# FAL65816_Backplane.net
KiCad netlist of a schematic drawn in EAGLE
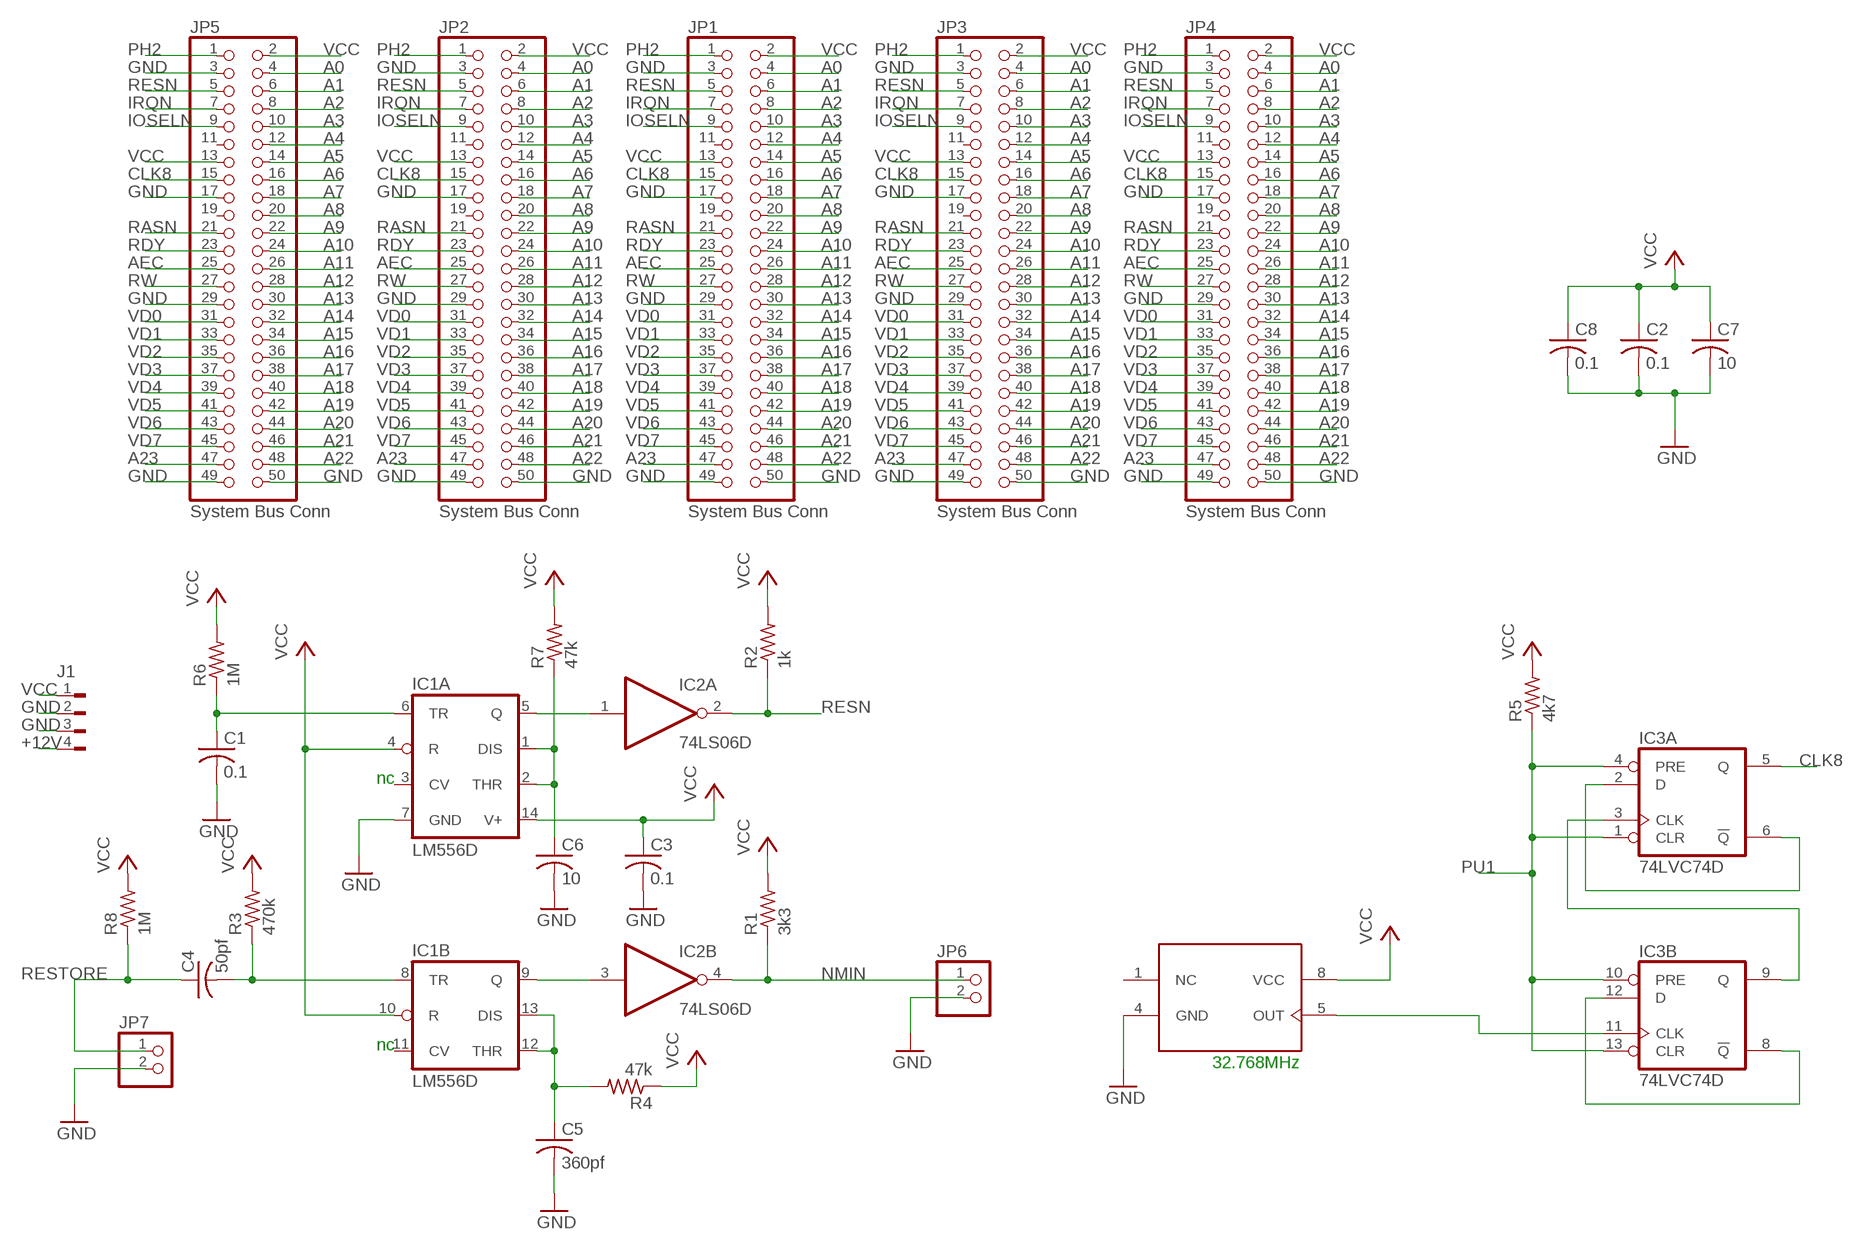
[diagram p0: schematic, sheet 1]

(export (version "E")
  (design (tool "Eeschema 10.0.6"))
  (components
    (comp (ref "C1")
      (value "0.1")
      (footprint "eagle-import:C050-024X044")
      (libsource (lib "eagle-import") (part "C-US050-024X044"))
    )
    (comp (ref "C2")
      (value "0.1")
      (footprint "eagle-import:C050-024X044")
      (libsource (lib "eagle-import") (part "C-US050-024X044"))
    )
    (comp (ref "C3")
      (value "0.1")
      (footprint "eagle-import:C050-024X044")
      (libsource (lib "eagle-import") (part "C-US050-024X044"))
    )
    (comp (ref "C4")
      (value "50pf")
      (footprint "eagle-import:C050-024X044")
      (libsource (lib "eagle-import") (part "C-US050-024X044"))
    )
    (comp (ref "C5")
      (value "360pf")
      (footprint "eagle-import:C050-024X044")
      (libsource (lib "eagle-import") (part "C-US050-024X044"))
    )
    (comp (ref "C6")
      (value "10")
      (footprint "eagle-import:C050-024X044")
      (libsource (lib "eagle-import") (part "C-US050-024X044"))
    )
    (comp (ref "C7")
      (value "10")
      (footprint "eagle-import:C050-024X044")
      (libsource (lib "eagle-import") (part "C-US050-024X044"))
    )
    (comp (ref "C8")
      (value "0.1")
      (footprint "eagle-import:C050-024X044")
      (libsource (lib "eagle-import") (part "C-US050-024X044"))
    )
    (comp (ref "IC1")
      (value "LM556D")
      (footprint "eagle-import:SO14")
      (libsource (lib "eagle-import") (part "556DLM"))
    )
    (comp (ref "IC2")
      (value "74LS06D")
      (footprint "eagle-import:SO14")
      (libsource (lib "eagle-import") (part "7406DLS"))
    )
    (comp (ref "IC3")
      (value "74LVC74D")
      (footprint "eagle-import:SO14")
      (libsource (lib "eagle-import") (part "7474DLS"))
    )
    (comp (ref "J1")
      (value "FLOPPY-4")
      (footprint "eagle-import:FLOPPY-4")
      (libsource (lib "eagle-import") (part "FLOPPY-4"))
    )
    (comp (ref "JP1")
      (value "System Bus Conn")
      (footprint "eagle-import:2X25")
      (libsource (lib "eagle-import") (part "PINHD-2X25"))
    )
    (comp (ref "JP2")
      (value "System Bus Conn")
      (footprint "eagle-import:2X25")
      (libsource (lib "eagle-import") (part "PINHD-2X25"))
    )
    (comp (ref "JP3")
      (value "System Bus Conn")
      (footprint "eagle-import:2X25")
      (libsource (lib "eagle-import") (part "PINHD-2X25"))
    )
    (comp (ref "JP4")
      (value "System Bus Conn")
      (footprint "eagle-import:2X25")
      (libsource (lib "eagle-import") (part "PINHD-2X25"))
    )
    (comp (ref "JP5")
      (value "System Bus Conn")
      (footprint "eagle-import:2X25")
      (libsource (lib "eagle-import") (part "PINHD-2X25"))
    )
    (comp (ref "JP6")
      (value "PINHD-1X2")
      (footprint "eagle-import:1X02")
      (libsource (lib "eagle-import") (part "PINHD-1X2"))
    )
    (comp (ref "JP7")
      (value "PINHD-1X2")
      (footprint "eagle-import:1X02")
      (libsource (lib "eagle-import") (part "PINHD-1X2"))
    )
    (comp (ref "R1")
      (value "3k3")
      (footprint "eagle-import:0204_7")
      (libsource (lib "eagle-import") (part "R-US_0204/7"))
    )
    (comp (ref "R2")
      (value "1k")
      (footprint "eagle-import:0204_7")
      (libsource (lib "eagle-import") (part "R-US_0204/7"))
    )
    (comp (ref "R3")
      (value "470k")
      (footprint "eagle-import:0204_7")
      (libsource (lib "eagle-import") (part "R-US_0204/7"))
    )
    (comp (ref "R4")
      (value "47k")
      (footprint "eagle-import:0204_7")
      (libsource (lib "eagle-import") (part "R-US_0204/7"))
    )
    (comp (ref "R5")
      (value "4k7")
      (footprint "eagle-import:0204_7")
      (libsource (lib "eagle-import") (part "R-US_0204/7"))
    )
    (comp (ref "R6")
      (value "1M")
      (footprint "eagle-import:0204_7")
      (libsource (lib "eagle-import") (part "R-US_0204/7"))
    )
    (comp (ref "R7")
      (value "47k")
      (footprint "eagle-import:0204_7")
      (libsource (lib "eagle-import") (part "R-US_0204/7"))
    )
    (comp (ref "R8")
      (value "1M")
      (footprint "eagle-import:0204_7")
      (libsource (lib "eagle-import") (part "R-US_0204/7"))
    )
    (comp (ref "U$1")
      (value "OSC")
      (footprint "eagle-import:DIL08")
      (libsource (lib "eagle-import") (part "OSC"))
    )
  )
  (nets
    (net (code "1") (name "/+12V") (class "Default")
      (node (ref "J1") (pin "4") (pinfunction "4_4") (pintype "passive"))
    )
    (net (code "2") (name "/A0") (class "Default")
      (node (ref "JP1") (pin "4") (pinfunction "4_4") (pintype "passive"))
      (node (ref "JP2") (pin "4") (pinfunction "4_4") (pintype "passive"))
      (node (ref "JP3") (pin "4") (pinfunction "4_4") (pintype "passive"))
      (node (ref "JP4") (pin "4") (pinfunction "4_4") (pintype "passive"))
      (node (ref "JP5") (pin "4") (pinfunction "4_4") (pintype "passive"))
    )
    (net (code "3") (name "/A1") (class "Default")
      (node (ref "JP1") (pin "6") (pinfunction "6_6") (pintype "passive"))
      (node (ref "JP2") (pin "6") (pinfunction "6_6") (pintype "passive"))
      (node (ref "JP3") (pin "6") (pinfunction "6_6") (pintype "passive"))
      (node (ref "JP4") (pin "6") (pinfunction "6_6") (pintype "passive"))
      (node (ref "JP5") (pin "6") (pinfunction "6_6") (pintype "passive"))
    )
    (net (code "4") (name "/A2") (class "Default")
      (node (ref "JP1") (pin "8") (pinfunction "8_8") (pintype "passive"))
      (node (ref "JP2") (pin "8") (pinfunction "8_8") (pintype "passive"))
      (node (ref "JP3") (pin "8") (pinfunction "8_8") (pintype "passive"))
      (node (ref "JP4") (pin "8") (pinfunction "8_8") (pintype "passive"))
      (node (ref "JP5") (pin "8") (pinfunction "8_8") (pintype "passive"))
    )
    (net (code "5") (name "/A3") (class "Default")
      (node (ref "JP1") (pin "10") (pinfunction "10_10") (pintype "passive"))
      (node (ref "JP2") (pin "10") (pinfunction "10_10") (pintype "passive"))
      (node (ref "JP3") (pin "10") (pinfunction "10_10") (pintype "passive"))
      (node (ref "JP4") (pin "10") (pinfunction "10_10") (pintype "passive"))
      (node (ref "JP5") (pin "10") (pinfunction "10_10") (pintype "passive"))
    )
    (net (code "6") (name "/A4") (class "Default")
      (node (ref "JP1") (pin "12") (pinfunction "12_12") (pintype "passive"))
      (node (ref "JP2") (pin "12") (pinfunction "12_12") (pintype "passive"))
      (node (ref "JP3") (pin "12") (pinfunction "12_12") (pintype "passive"))
      (node (ref "JP4") (pin "12") (pinfunction "12_12") (pintype "passive"))
      (node (ref "JP5") (pin "12") (pinfunction "12_12") (pintype "passive"))
    )
    (net (code "7") (name "/A5") (class "Default")
      (node (ref "JP1") (pin "14") (pinfunction "14_14") (pintype "passive"))
      (node (ref "JP2") (pin "14") (pinfunction "14_14") (pintype "passive"))
      (node (ref "JP3") (pin "14") (pinfunction "14_14") (pintype "passive"))
      (node (ref "JP4") (pin "14") (pinfunction "14_14") (pintype "passive"))
      (node (ref "JP5") (pin "14") (pinfunction "14_14") (pintype "passive"))
    )
    (net (code "8") (name "/A6") (class "Default")
      (node (ref "JP1") (pin "16") (pinfunction "16_16") (pintype "passive"))
      (node (ref "JP2") (pin "16") (pinfunction "16_16") (pintype "passive"))
      (node (ref "JP3") (pin "16") (pinfunction "16_16") (pintype "passive"))
      (node (ref "JP4") (pin "16") (pinfunction "16_16") (pintype "passive"))
      (node (ref "JP5") (pin "16") (pinfunction "16_16") (pintype "passive"))
    )
    (net (code "9") (name "/A7") (class "Default")
      (node (ref "JP1") (pin "18") (pinfunction "18_18") (pintype "passive"))
      (node (ref "JP2") (pin "18") (pinfunction "18_18") (pintype "passive"))
      (node (ref "JP3") (pin "18") (pinfunction "18_18") (pintype "passive"))
      (node (ref "JP4") (pin "18") (pinfunction "18_18") (pintype "passive"))
      (node (ref "JP5") (pin "18") (pinfunction "18_18") (pintype "passive"))
    )
    (net (code "10") (name "/A8") (class "Default")
      (node (ref "JP1") (pin "20") (pinfunction "20_20") (pintype "passive"))
      (node (ref "JP2") (pin "20") (pinfunction "20_20") (pintype "passive"))
      (node (ref "JP3") (pin "20") (pinfunction "20_20") (pintype "passive"))
      (node (ref "JP4") (pin "20") (pinfunction "20_20") (pintype "passive"))
      (node (ref "JP5") (pin "20") (pinfunction "20_20") (pintype "passive"))
    )
    (net (code "11") (name "/A9") (class "Default")
      (node (ref "JP1") (pin "22") (pinfunction "22_22") (pintype "passive"))
      (node (ref "JP2") (pin "22") (pinfunction "22_22") (pintype "passive"))
      (node (ref "JP3") (pin "22") (pinfunction "22_22") (pintype "passive"))
      (node (ref "JP4") (pin "22") (pinfunction "22_22") (pintype "passive"))
      (node (ref "JP5") (pin "22") (pinfunction "22_22") (pintype "passive"))
    )
    (net (code "12") (name "/A10") (class "Default")
      (node (ref "JP1") (pin "24") (pinfunction "24_24") (pintype "passive"))
      (node (ref "JP2") (pin "24") (pinfunction "24_24") (pintype "passive"))
      (node (ref "JP3") (pin "24") (pinfunction "24_24") (pintype "passive"))
      (node (ref "JP4") (pin "24") (pinfunction "24_24") (pintype "passive"))
      (node (ref "JP5") (pin "24") (pinfunction "24_24") (pintype "passive"))
    )
    (net (code "13") (name "/A11") (class "Default")
      (node (ref "JP1") (pin "26") (pinfunction "26_26") (pintype "passive"))
      (node (ref "JP2") (pin "26") (pinfunction "26_26") (pintype "passive"))
      (node (ref "JP3") (pin "26") (pinfunction "26_26") (pintype "passive"))
      (node (ref "JP4") (pin "26") (pinfunction "26_26") (pintype "passive"))
      (node (ref "JP5") (pin "26") (pinfunction "26_26") (pintype "passive"))
    )
    (net (code "14") (name "/A12") (class "Default")
      (node (ref "JP1") (pin "28") (pinfunction "28_28") (pintype "passive"))
      (node (ref "JP2") (pin "28") (pinfunction "28_28") (pintype "passive"))
      (node (ref "JP3") (pin "28") (pinfunction "28_28") (pintype "passive"))
      (node (ref "JP4") (pin "28") (pinfunction "28_28") (pintype "passive"))
      (node (ref "JP5") (pin "28") (pinfunction "28_28") (pintype "passive"))
    )
    (net (code "15") (name "/A13") (class "Default")
      (node (ref "JP1") (pin "30") (pinfunction "30_30") (pintype "passive"))
      (node (ref "JP2") (pin "30") (pinfunction "30_30") (pintype "passive"))
      (node (ref "JP3") (pin "30") (pinfunction "30_30") (pintype "passive"))
      (node (ref "JP4") (pin "30") (pinfunction "30_30") (pintype "passive"))
      (node (ref "JP5") (pin "30") (pinfunction "30_30") (pintype "passive"))
    )
    (net (code "16") (name "/A14") (class "Default")
      (node (ref "JP1") (pin "32") (pinfunction "32_32") (pintype "passive"))
      (node (ref "JP2") (pin "32") (pinfunction "32_32") (pintype "passive"))
      (node (ref "JP3") (pin "32") (pinfunction "32_32") (pintype "passive"))
      (node (ref "JP4") (pin "32") (pinfunction "32_32") (pintype "passive"))
      (node (ref "JP5") (pin "32") (pinfunction "32_32") (pintype "passive"))
    )
    (net (code "17") (name "/A15") (class "Default")
      (node (ref "JP1") (pin "34") (pinfunction "34_34") (pintype "passive"))
      (node (ref "JP2") (pin "34") (pinfunction "34_34") (pintype "passive"))
      (node (ref "JP3") (pin "34") (pinfunction "34_34") (pintype "passive"))
      (node (ref "JP4") (pin "34") (pinfunction "34_34") (pintype "passive"))
      (node (ref "JP5") (pin "34") (pinfunction "34_34") (pintype "passive"))
    )
    (net (code "18") (name "/A16") (class "Default")
      (node (ref "JP1") (pin "36") (pinfunction "36_36") (pintype "passive"))
      (node (ref "JP2") (pin "36") (pinfunction "36_36") (pintype "passive"))
      (node (ref "JP3") (pin "36") (pinfunction "36_36") (pintype "passive"))
      (node (ref "JP4") (pin "36") (pinfunction "36_36") (pintype "passive"))
      (node (ref "JP5") (pin "36") (pinfunction "36_36") (pintype "passive"))
    )
    (net (code "19") (name "/A17") (class "Default")
      (node (ref "JP1") (pin "38") (pinfunction "38_38") (pintype "passive"))
      (node (ref "JP2") (pin "38") (pinfunction "38_38") (pintype "passive"))
      (node (ref "JP3") (pin "38") (pinfunction "38_38") (pintype "passive"))
      (node (ref "JP4") (pin "38") (pinfunction "38_38") (pintype "passive"))
      (node (ref "JP5") (pin "38") (pinfunction "38_38") (pintype "passive"))
    )
    (net (code "20") (name "/A18") (class "Default")
      (node (ref "JP1") (pin "40") (pinfunction "40_40") (pintype "passive"))
      (node (ref "JP2") (pin "40") (pinfunction "40_40") (pintype "passive"))
      (node (ref "JP3") (pin "40") (pinfunction "40_40") (pintype "passive"))
      (node (ref "JP4") (pin "40") (pinfunction "40_40") (pintype "passive"))
      (node (ref "JP5") (pin "40") (pinfunction "40_40") (pintype "passive"))
    )
    (net (code "21") (name "/A19") (class "Default")
      (node (ref "JP1") (pin "42") (pinfunction "42_42") (pintype "passive"))
      (node (ref "JP2") (pin "42") (pinfunction "42_42") (pintype "passive"))
      (node (ref "JP3") (pin "42") (pinfunction "42_42") (pintype "passive"))
      (node (ref "JP4") (pin "42") (pinfunction "42_42") (pintype "passive"))
      (node (ref "JP5") (pin "42") (pinfunction "42_42") (pintype "passive"))
    )
    (net (code "22") (name "/A20") (class "Default")
      (node (ref "JP1") (pin "44") (pinfunction "44_44") (pintype "passive"))
      (node (ref "JP2") (pin "44") (pinfunction "44_44") (pintype "passive"))
      (node (ref "JP3") (pin "44") (pinfunction "44_44") (pintype "passive"))
      (node (ref "JP4") (pin "44") (pinfunction "44_44") (pintype "passive"))
      (node (ref "JP5") (pin "44") (pinfunction "44_44") (pintype "passive"))
    )
    (net (code "23") (name "/A21") (class "Default")
      (node (ref "JP1") (pin "46") (pinfunction "46_46") (pintype "passive"))
      (node (ref "JP2") (pin "46") (pinfunction "46_46") (pintype "passive"))
      (node (ref "JP3") (pin "46") (pinfunction "46_46") (pintype "passive"))
      (node (ref "JP4") (pin "46") (pinfunction "46_46") (pintype "passive"))
      (node (ref "JP5") (pin "46") (pinfunction "46_46") (pintype "passive"))
    )
    (net (code "24") (name "/A22") (class "Default")
      (node (ref "JP1") (pin "48") (pinfunction "48_48") (pintype "passive"))
      (node (ref "JP2") (pin "48") (pinfunction "48_48") (pintype "passive"))
      (node (ref "JP3") (pin "48") (pinfunction "48_48") (pintype "passive"))
      (node (ref "JP4") (pin "48") (pinfunction "48_48") (pintype "passive"))
      (node (ref "JP5") (pin "48") (pinfunction "48_48") (pintype "passive"))
    )
    (net (code "25") (name "/A23") (class "Default")
      (node (ref "JP1") (pin "47") (pinfunction "47_47") (pintype "passive"))
      (node (ref "JP2") (pin "47") (pinfunction "47_47") (pintype "passive"))
      (node (ref "JP3") (pin "47") (pinfunction "47_47") (pintype "passive"))
      (node (ref "JP4") (pin "47") (pinfunction "47_47") (pintype "passive"))
      (node (ref "JP5") (pin "47") (pinfunction "47_47") (pintype "passive"))
    )
    (net (code "26") (name "/AEC") (class "Default")
      (node (ref "JP1") (pin "25") (pinfunction "25_25") (pintype "passive"))
      (node (ref "JP2") (pin "25") (pinfunction "25_25") (pintype "passive"))
      (node (ref "JP3") (pin "25") (pinfunction "25_25") (pintype "passive"))
      (node (ref "JP4") (pin "25") (pinfunction "25_25") (pintype "passive"))
      (node (ref "JP5") (pin "25") (pinfunction "25_25") (pintype "passive"))
    )
    (net (code "27") (name "/CLK8") (class "Default")
      (node (ref "IC3") (pin "5") (pinfunction "Q_5") (pintype "output"))
      (node (ref "JP1") (pin "15") (pinfunction "15_15") (pintype "passive"))
      (node (ref "JP2") (pin "15") (pinfunction "15_15") (pintype "passive"))
      (node (ref "JP3") (pin "15") (pinfunction "15_15") (pintype "passive"))
      (node (ref "JP4") (pin "15") (pinfunction "15_15") (pintype "passive"))
      (node (ref "JP5") (pin "15") (pinfunction "15_15") (pintype "passive"))
    )
    (net (code "28") (name "/IOSELN") (class "Default")
      (node (ref "JP1") (pin "9") (pinfunction "9_9") (pintype "passive"))
      (node (ref "JP2") (pin "9") (pinfunction "9_9") (pintype "passive"))
      (node (ref "JP3") (pin "9") (pinfunction "9_9") (pintype "passive"))
      (node (ref "JP4") (pin "9") (pinfunction "9_9") (pintype "passive"))
      (node (ref "JP5") (pin "9") (pinfunction "9_9") (pintype "passive"))
    )
    (net (code "29") (name "/IRQN") (class "Default")
      (node (ref "JP1") (pin "7") (pinfunction "7_7") (pintype "passive"))
      (node (ref "JP2") (pin "7") (pinfunction "7_7") (pintype "passive"))
      (node (ref "JP3") (pin "7") (pinfunction "7_7") (pintype "passive"))
      (node (ref "JP4") (pin "7") (pinfunction "7_7") (pintype "passive"))
      (node (ref "JP5") (pin "7") (pinfunction "7_7") (pintype "passive"))
    )
    (net (code "30") (name "/NMIN") (class "Default")
      (node (ref "IC2") (pin "4") (pinfunction "O_4") (pintype "open_collector"))
      (node (ref "JP6") (pin "1") (pinfunction "1_1") (pintype "passive"))
      (node (ref "R1") (pin "1") (pinfunction "1_1") (pintype "passive"))
    )
    (net (code "31") (name "/PH2") (class "Default")
      (node (ref "JP1") (pin "1") (pinfunction "1_1") (pintype "passive"))
      (node (ref "JP2") (pin "1") (pinfunction "1_1") (pintype "passive"))
      (node (ref "JP3") (pin "1") (pinfunction "1_1") (pintype "passive"))
      (node (ref "JP4") (pin "1") (pinfunction "1_1") (pintype "passive"))
      (node (ref "JP5") (pin "1") (pinfunction "1_1") (pintype "passive"))
    )
    (net (code "32") (name "/PU1") (class "Default")
      (node (ref "IC3") (pin "1") (pinfunction "CLR_1") (pintype "input"))
      (node (ref "IC3") (pin "10") (pinfunction "PRE_10") (pintype "input"))
      (node (ref "IC3") (pin "13") (pinfunction "CLR_13") (pintype "input"))
      (node (ref "IC3") (pin "4") (pinfunction "PRE_4") (pintype "input"))
      (node (ref "R5") (pin "1") (pinfunction "1_1") (pintype "passive"))
    )
    (net (code "33") (name "/RASN") (class "Default")
      (node (ref "JP1") (pin "21") (pinfunction "21_21") (pintype "passive"))
      (node (ref "JP2") (pin "21") (pinfunction "21_21") (pintype "passive"))
      (node (ref "JP3") (pin "21") (pinfunction "21_21") (pintype "passive"))
      (node (ref "JP4") (pin "21") (pinfunction "21_21") (pintype "passive"))
      (node (ref "JP5") (pin "21") (pinfunction "21_21") (pintype "passive"))
    )
    (net (code "34") (name "/RDY") (class "Default")
      (node (ref "JP1") (pin "23") (pinfunction "23_23") (pintype "passive"))
      (node (ref "JP2") (pin "23") (pinfunction "23_23") (pintype "passive"))
      (node (ref "JP3") (pin "23") (pinfunction "23_23") (pintype "passive"))
      (node (ref "JP4") (pin "23") (pinfunction "23_23") (pintype "passive"))
      (node (ref "JP5") (pin "23") (pinfunction "23_23") (pintype "passive"))
    )
    (net (code "35") (name "/RESN") (class "Default")
      (node (ref "IC2") (pin "2") (pinfunction "O_2") (pintype "open_collector"))
      (node (ref "JP1") (pin "5") (pinfunction "5_5") (pintype "passive"))
      (node (ref "JP2") (pin "5") (pinfunction "5_5") (pintype "passive"))
      (node (ref "JP3") (pin "5") (pinfunction "5_5") (pintype "passive"))
      (node (ref "JP4") (pin "5") (pinfunction "5_5") (pintype "passive"))
      (node (ref "JP5") (pin "5") (pinfunction "5_5") (pintype "passive"))
      (node (ref "R2") (pin "1") (pinfunction "1_1") (pintype "passive"))
    )
    (net (code "36") (name "/RESTORE") (class "Default")
      (node (ref "C4") (pin "1") (pinfunction "1_1") (pintype "passive"))
      (node (ref "JP7") (pin "1") (pinfunction "1_1") (pintype "passive"))
      (node (ref "R8") (pin "1") (pinfunction "1_1") (pintype "passive"))
    )
    (net (code "37") (name "/RW") (class "Default")
      (node (ref "JP1") (pin "27") (pinfunction "27_27") (pintype "passive"))
      (node (ref "JP2") (pin "27") (pinfunction "27_27") (pintype "passive"))
      (node (ref "JP3") (pin "27") (pinfunction "27_27") (pintype "passive"))
      (node (ref "JP4") (pin "27") (pinfunction "27_27") (pintype "passive"))
      (node (ref "JP5") (pin "27") (pinfunction "27_27") (pintype "passive"))
    )
    (net (code "38") (name "/VD0") (class "Default")
      (node (ref "JP1") (pin "31") (pinfunction "31_31") (pintype "passive"))
      (node (ref "JP2") (pin "31") (pinfunction "31_31") (pintype "passive"))
      (node (ref "JP3") (pin "31") (pinfunction "31_31") (pintype "passive"))
      (node (ref "JP4") (pin "31") (pinfunction "31_31") (pintype "passive"))
      (node (ref "JP5") (pin "31") (pinfunction "31_31") (pintype "passive"))
    )
    (net (code "39") (name "/VD1") (class "Default")
      (node (ref "JP1") (pin "33") (pinfunction "33_33") (pintype "passive"))
      (node (ref "JP2") (pin "33") (pinfunction "33_33") (pintype "passive"))
      (node (ref "JP3") (pin "33") (pinfunction "33_33") (pintype "passive"))
      (node (ref "JP4") (pin "33") (pinfunction "33_33") (pintype "passive"))
      (node (ref "JP5") (pin "33") (pinfunction "33_33") (pintype "passive"))
    )
    (net (code "40") (name "/VD2") (class "Default")
      (node (ref "JP1") (pin "35") (pinfunction "35_35") (pintype "passive"))
      (node (ref "JP2") (pin "35") (pinfunction "35_35") (pintype "passive"))
      (node (ref "JP3") (pin "35") (pinfunction "35_35") (pintype "passive"))
      (node (ref "JP4") (pin "35") (pinfunction "35_35") (pintype "passive"))
      (node (ref "JP5") (pin "35") (pinfunction "35_35") (pintype "passive"))
    )
    (net (code "41") (name "/VD3") (class "Default")
      (node (ref "JP1") (pin "37") (pinfunction "37_37") (pintype "passive"))
      (node (ref "JP2") (pin "37") (pinfunction "37_37") (pintype "passive"))
      (node (ref "JP3") (pin "37") (pinfunction "37_37") (pintype "passive"))
      (node (ref "JP4") (pin "37") (pinfunction "37_37") (pintype "passive"))
      (node (ref "JP5") (pin "37") (pinfunction "37_37") (pintype "passive"))
    )
    (net (code "42") (name "/VD4") (class "Default")
      (node (ref "JP1") (pin "39") (pinfunction "39_39") (pintype "passive"))
      (node (ref "JP2") (pin "39") (pinfunction "39_39") (pintype "passive"))
      (node (ref "JP3") (pin "39") (pinfunction "39_39") (pintype "passive"))
      (node (ref "JP4") (pin "39") (pinfunction "39_39") (pintype "passive"))
      (node (ref "JP5") (pin "39") (pinfunction "39_39") (pintype "passive"))
    )
    (net (code "43") (name "/VD5") (class "Default")
      (node (ref "JP1") (pin "41") (pinfunction "41_41") (pintype "passive"))
      (node (ref "JP2") (pin "41") (pinfunction "41_41") (pintype "passive"))
      (node (ref "JP3") (pin "41") (pinfunction "41_41") (pintype "passive"))
      (node (ref "JP4") (pin "41") (pinfunction "41_41") (pintype "passive"))
      (node (ref "JP5") (pin "41") (pinfunction "41_41") (pintype "passive"))
    )
    (net (code "44") (name "/VD6") (class "Default")
      (node (ref "JP1") (pin "43") (pinfunction "43_43") (pintype "passive"))
      (node (ref "JP2") (pin "43") (pinfunction "43_43") (pintype "passive"))
      (node (ref "JP3") (pin "43") (pinfunction "43_43") (pintype "passive"))
      (node (ref "JP4") (pin "43") (pinfunction "43_43") (pintype "passive"))
      (node (ref "JP5") (pin "43") (pinfunction "43_43") (pintype "passive"))
    )
    (net (code "45") (name "/VD7") (class "Default")
      (node (ref "JP1") (pin "45") (pinfunction "45_45") (pintype "passive"))
      (node (ref "JP2") (pin "45") (pinfunction "45_45") (pintype "passive"))
      (node (ref "JP3") (pin "45") (pinfunction "45_45") (pintype "passive"))
      (node (ref "JP4") (pin "45") (pinfunction "45_45") (pintype "passive"))
      (node (ref "JP5") (pin "45") (pinfunction "45_45") (pintype "passive"))
    )
    (net (code "46") (name "GND") (class "Default")
      (node (ref "C1") (pin "2") (pinfunction "2_2") (pintype "passive"))
      (node (ref "C2") (pin "2") (pinfunction "2_2") (pintype "passive"))
      (node (ref "C3") (pin "2") (pinfunction "2_2") (pintype "passive"))
      (node (ref "C5") (pin "2") (pinfunction "2_2") (pintype "passive"))
      (node (ref "C6") (pin "2") (pinfunction "2_2") (pintype "passive"))
      (node (ref "C7") (pin "2") (pinfunction "2_2") (pintype "passive"))
      (node (ref "C8") (pin "2") (pinfunction "2_2") (pintype "passive"))
      (node (ref "IC1") (pin "7") (pinfunction "GND_7") (pintype "power_in"))
      (node (ref "J1") (pin "2") (pinfunction "2_2") (pintype "passive"))
      (node (ref "J1") (pin "3") (pinfunction "3_3") (pintype "passive"))
      (node (ref "JP1") (pin "17") (pinfunction "17_17") (pintype "passive"))
      (node (ref "JP1") (pin "29") (pinfunction "29_29") (pintype "passive"))
      (node (ref "JP1") (pin "3") (pinfunction "3_3") (pintype "passive"))
      (node (ref "JP1") (pin "49") (pinfunction "49_49") (pintype "passive"))
      (node (ref "JP1") (pin "50") (pinfunction "50_50") (pintype "passive"))
      (node (ref "JP2") (pin "17") (pinfunction "17_17") (pintype "passive"))
      (node (ref "JP2") (pin "29") (pinfunction "29_29") (pintype "passive"))
      (node (ref "JP2") (pin "3") (pinfunction "3_3") (pintype "passive"))
      (node (ref "JP2") (pin "49") (pinfunction "49_49") (pintype "passive"))
      (node (ref "JP2") (pin "50") (pinfunction "50_50") (pintype "passive"))
      (node (ref "JP3") (pin "17") (pinfunction "17_17") (pintype "passive"))
      (node (ref "JP3") (pin "29") (pinfunction "29_29") (pintype "passive"))
      (node (ref "JP3") (pin "3") (pinfunction "3_3") (pintype "passive"))
      (node (ref "JP3") (pin "49") (pinfunction "49_49") (pintype "passive"))
      (node (ref "JP3") (pin "50") (pinfunction "50_50") (pintype "passive"))
      (node (ref "JP4") (pin "17") (pinfunction "17_17") (pintype "passive"))
      (node (ref "JP4") (pin "29") (pinfunction "29_29") (pintype "passive"))
      (node (ref "JP4") (pin "3") (pinfunction "3_3") (pintype "passive"))
      (node (ref "JP4") (pin "49") (pinfunction "49_49") (pintype "passive"))
      (node (ref "JP4") (pin "50") (pinfunction "50_50") (pintype "passive"))
      (node (ref "JP5") (pin "17") (pinfunction "17_17") (pintype "passive"))
      (node (ref "JP5") (pin "29") (pinfunction "29_29") (pintype "passive"))
      (node (ref "JP5") (pin "3") (pinfunction "3_3") (pintype "passive"))
      (node (ref "JP5") (pin "49") (pinfunction "49_49") (pintype "passive"))
      (node (ref "JP5") (pin "50") (pinfunction "50_50") (pintype "passive"))
      (node (ref "JP6") (pin "2") (pinfunction "2_2") (pintype "passive"))
      (node (ref "JP7") (pin "2") (pinfunction "2_2") (pintype "passive"))
      (node (ref "U$1") (pin "4") (pinfunction "GND_4") (pintype "power_in"))
    )
    (net (code "47") (name "Net-(IC1A-DIS)") (class "Default")
      (node (ref "C6") (pin "1") (pinfunction "1_1") (pintype "passive"))
      (node (ref "IC1") (pin "1") (pinfunction "DIS_1") (pintype "input"))
      (node (ref "IC1") (pin "2") (pinfunction "THR_2") (pintype "input"))
      (node (ref "R7") (pin "1") (pinfunction "1_1") (pintype "passive"))
    )
    (net (code "48") (name "Net-(IC1A-Q)") (class "Default")
      (node (ref "IC1") (pin "5") (pinfunction "Q_5") (pintype "output"))
      (node (ref "IC2") (pin "1") (pinfunction "I_1") (pintype "input"))
    )
    (net (code "49") (name "Net-(IC1A-TR)") (class "Default")
      (node (ref "C1") (pin "1") (pinfunction "1_1") (pintype "passive"))
      (node (ref "IC1") (pin "6") (pinfunction "TR_6") (pintype "input"))
      (node (ref "R6") (pin "1") (pinfunction "1_1") (pintype "passive"))
    )
    (net (code "50") (name "Net-(IC1B-DIS)") (class "Default")
      (node (ref "C5") (pin "1") (pinfunction "1_1") (pintype "passive"))
      (node (ref "IC1") (pin "12") (pinfunction "THR_12") (pintype "input"))
      (node (ref "IC1") (pin "13") (pinfunction "DIS_13") (pintype "input"))
      (node (ref "R4") (pin "2") (pinfunction "2_2") (pintype "passive"))
    )
    (net (code "51") (name "Net-(IC1B-Q)") (class "Default")
      (node (ref "IC1") (pin "9") (pinfunction "Q_9") (pintype "output"))
      (node (ref "IC2") (pin "3") (pinfunction "I_3") (pintype "input"))
    )
    (net (code "52") (name "Net-(IC1B-TR)") (class "Default")
      (node (ref "C4") (pin "2") (pinfunction "2_2") (pintype "passive"))
      (node (ref "IC1") (pin "8") (pinfunction "TR_8") (pintype "input"))
      (node (ref "R3") (pin "1") (pinfunction "1_1") (pintype "passive"))
    )
    (net (code "53") (name "Net-(IC3A-CLK)") (class "Default")
      (node (ref "IC3") (pin "3") (pinfunction "CLK_3") (pintype "input"))
      (node (ref "IC3") (pin "9") (pinfunction "Q_9") (pintype "output"))
    )
    (net (code "54") (name "Net-(IC3A-D)") (class "Default")
      (node (ref "IC3") (pin "2") (pinfunction "D_2") (pintype "input"))
      (node (ref "IC3") (pin "6") (pinfunction "~{Q}_6") (pintype "output"))
    )
    (net (code "55") (name "Net-(IC3B-CLK)") (class "Default")
      (node (ref "IC3") (pin "11") (pinfunction "CLK_11") (pintype "input"))
      (node (ref "U$1") (pin "5") (pinfunction "OUT_5") (pintype "output"))
    )
    (net (code "56") (name "Net-(IC3B-D)") (class "Default")
      (node (ref "IC3") (pin "12") (pinfunction "D_12") (pintype "input"))
      (node (ref "IC3") (pin "8") (pinfunction "~{Q}_8") (pintype "output"))
    )
    (net (code "57") (name "VCC") (class "Default")
      (node (ref "C2") (pin "1") (pinfunction "1_1") (pintype "passive"))
      (node (ref "C3") (pin "1") (pinfunction "1_1") (pintype "passive"))
      (node (ref "C7") (pin "1") (pinfunction "1_1") (pintype "passive"))
      (node (ref "C8") (pin "1") (pinfunction "1_1") (pintype "passive"))
      (node (ref "IC1") (pin "10") (pinfunction "R_10") (pintype "input"))
      (node (ref "IC1") (pin "14") (pinfunction "V+_14") (pintype "power_in"))
      (node (ref "IC1") (pin "4") (pinfunction "R_4") (pintype "input"))
      (node (ref "J1") (pin "1") (pinfunction "1_1") (pintype "passive"))
      (node (ref "JP1") (pin "13") (pinfunction "13_13") (pintype "passive"))
      (node (ref "JP1") (pin "2") (pinfunction "2_2") (pintype "passive"))
      (node (ref "JP2") (pin "13") (pinfunction "13_13") (pintype "passive"))
      (node (ref "JP2") (pin "2") (pinfunction "2_2") (pintype "passive"))
      (node (ref "JP3") (pin "13") (pinfunction "13_13") (pintype "passive"))
      (node (ref "JP3") (pin "2") (pinfunction "2_2") (pintype "passive"))
      (node (ref "JP4") (pin "13") (pinfunction "13_13") (pintype "passive"))
      (node (ref "JP4") (pin "2") (pinfunction "2_2") (pintype "passive"))
      (node (ref "JP5") (pin "13") (pinfunction "13_13") (pintype "passive"))
      (node (ref "JP5") (pin "2") (pinfunction "2_2") (pintype "passive"))
      (node (ref "R1") (pin "2") (pinfunction "2_2") (pintype "passive"))
      (node (ref "R2") (pin "2") (pinfunction "2_2") (pintype "passive"))
      (node (ref "R3") (pin "2") (pinfunction "2_2") (pintype "passive"))
      (node (ref "R4") (pin "1") (pinfunction "1_1") (pintype "passive"))
      (node (ref "R5") (pin "2") (pinfunction "2_2") (pintype "passive"))
      (node (ref "R6") (pin "2") (pinfunction "2_2") (pintype "passive"))
      (node (ref "R7") (pin "2") (pinfunction "2_2") (pintype "passive"))
      (node (ref "R8") (pin "2") (pinfunction "2_2") (pintype "passive"))
      (node (ref "U$1") (pin "8") (pinfunction "VCC_8") (pintype "power_in"))
    )
    (net (code "58") (name "unconnected-(IC1A-CV-Pad3)") (class "Default")
      (node (ref "IC1") (pin "3") (pinfunction "CV_3") (pintype "input"))
    )
    (net (code "59") (name "unconnected-(IC1B-CV-Pad11)") (class "Default")
      (node (ref "IC1") (pin "11") (pinfunction "CV_11") (pintype "input"))
    )
    (net (code "60") (name "unconnected-(JP1-Pad11)") (class "Default")
      (node (ref "JP1") (pin "11") (pinfunction "11_11") (pintype "passive"))
    )
    (net (code "61") (name "unconnected-(JP1-Pad19)") (class "Default")
      (node (ref "JP1") (pin "19") (pinfunction "19_19") (pintype "passive"))
    )
    (net (code "62") (name "unconnected-(JP2-Pad11)") (class "Default")
      (node (ref "JP2") (pin "11") (pinfunction "11_11") (pintype "passive"))
    )
    (net (code "63") (name "unconnected-(JP2-Pad19)") (class "Default")
      (node (ref "JP2") (pin "19") (pinfunction "19_19") (pintype "passive"))
    )
    (net (code "64") (name "unconnected-(JP3-Pad11)") (class "Default")
      (node (ref "JP3") (pin "11") (pinfunction "11_11") (pintype "passive"))
    )
    (net (code "65") (name "unconnected-(JP3-Pad19)") (class "Default")
      (node (ref "JP3") (pin "19") (pinfunction "19_19") (pintype "passive"))
    )
    (net (code "66") (name "unconnected-(JP4-Pad11)") (class "Default")
      (node (ref "JP4") (pin "11") (pinfunction "11_11") (pintype "passive"))
    )
    (net (code "67") (name "unconnected-(JP4-Pad19)") (class "Default")
      (node (ref "JP4") (pin "19") (pinfunction "19_19") (pintype "passive"))
    )
    (net (code "68") (name "unconnected-(JP5-Pad11)") (class "Default")
      (node (ref "JP5") (pin "11") (pinfunction "11_11") (pintype "passive"))
    )
    (net (code "69") (name "unconnected-(JP5-Pad19)") (class "Default")
      (node (ref "JP5") (pin "19") (pinfunction "19_19") (pintype "passive"))
    )
    (net (code "70") (name "unconnected-(U$1-NC-Pad1)") (class "Default")
      (node (ref "U$1") (pin "1") (pinfunction "NC_1") (pintype "bidirectional"))
    )
  )
)
